# SCH_arduino-nano-every-sheild_2024-02-21.net
KiCad netlist of a schematic drawn in EasyEDA
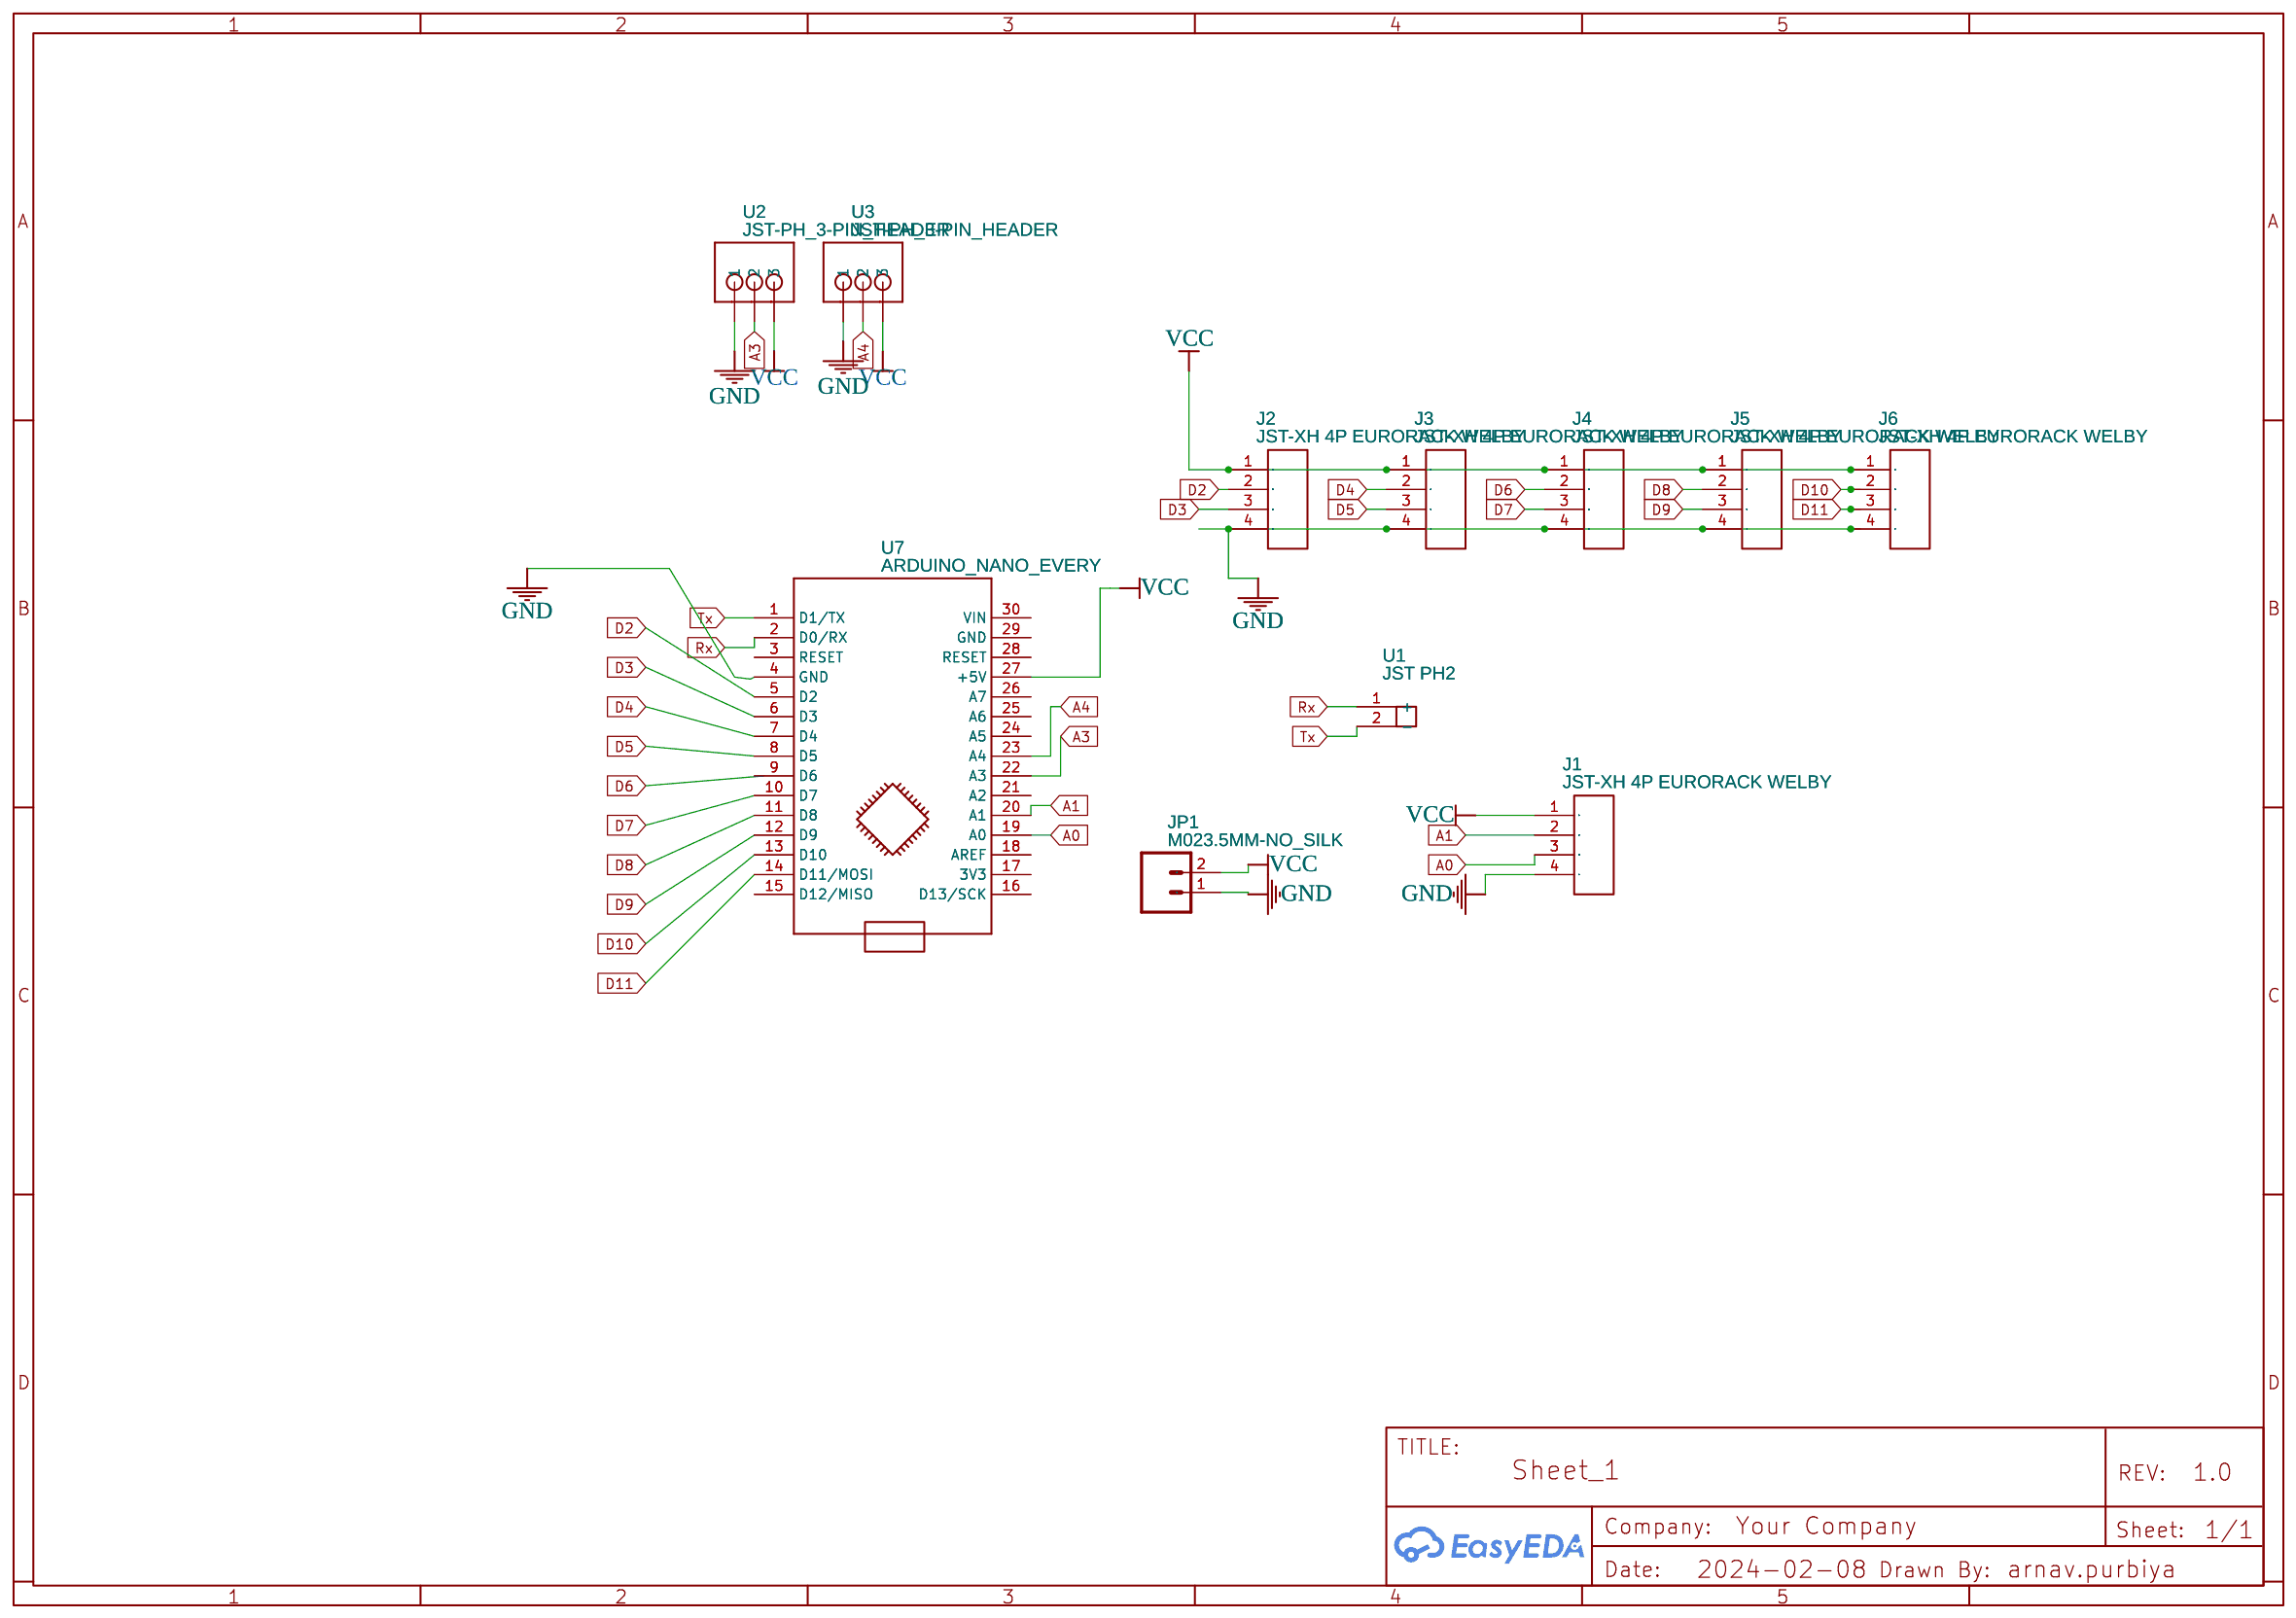
[diagram p0: schematic sheet]

(export (version "E")
  (design (tool "Eeschema 10.0.6"))
  (components
    (comp (ref "J1")
      (value "JST-XH 4P EURORACK WELBY")
      (libsource (lib "") (part "JST-XH 4P EURORACK WELBY"))
    )
    (comp (ref "J2")
      (value "JST-XH 4P EURORACK WELBY")
      (libsource (lib "") (part "JST-XH 4P EURORACK WELBY"))
    )
    (comp (ref "J3")
      (value "JST-XH 4P EURORACK WELBY")
      (libsource (lib "") (part "JST-XH 4P EURORACK WELBY"))
    )
    (comp (ref "J4")
      (value "JST-XH 4P EURORACK WELBY")
      (libsource (lib "") (part "JST-XH 4P EURORACK WELBY"))
    )
    (comp (ref "J5")
      (value "JST-XH 4P EURORACK WELBY")
      (libsource (lib "") (part "JST-XH 4P EURORACK WELBY"))
    )
    (comp (ref "J6")
      (value "JST-XH 4P EURORACK WELBY")
      (libsource (lib "") (part "JST-XH 4P EURORACK WELBY"))
    )
    (comp (ref "JP1") (value "M023.5MM-NO_SILK") (libsource (lib "") (part "M023.5MM-NO_SILK")))
    (comp (ref "U1") (value "JST PH2") (libsource (lib "") (part "JST PH2")))
    (comp (ref "U2") (value "JST-PH_3-PIN_HEADER") (libsource (lib "") (part "JST-PH_3-PIN_HEADER")))
    (comp (ref "U3") (value "JST-PH_3-PIN_HEADER") (libsource (lib "") (part "JST-PH_3-PIN_HEADER")))
    (comp (ref "U7") (value "ARDUINO_NANO_EVERY") (libsource (lib "") (part "ARDUINO_NANO_EVERY")))
  )
  (nets
    (net (code "1") (name "A0") (class "Default")
      (node (ref "J1") (pin "3") (pinfunction "3_3") (pintype "unspecified"))
      (node (ref "U7") (pin "19") (pinfunction "A0_19") (pintype "unspecified"))
    )
    (net (code "2") (name "A1") (class "Default")
      (node (ref "J1") (pin "2") (pinfunction "2_2") (pintype "unspecified"))
      (node (ref "U7") (pin "20") (pinfunction "A1_20") (pintype "unspecified"))
    )
    (net (code "3") (name "A3") (class "Default")
      (node (ref "U2") (pin "P2") (pinfunction "2_P2") (pintype "unspecified"))
      (node (ref "U7") (pin "22") (pinfunction "A3_22") (pintype "unspecified"))
    )
    (net (code "4") (name "A4") (class "Default")
      (node (ref "U3") (pin "P2") (pinfunction "2_P2") (pintype "unspecified"))
      (node (ref "U7") (pin "23") (pinfunction "A4_23") (pintype "unspecified"))
    )
    (net (code "5") (name "D2") (class "Default")
      (node (ref "J2") (pin "2") (pinfunction "2_2") (pintype "unspecified"))
      (node (ref "U7") (pin "5") (pinfunction "D2_5") (pintype "unspecified"))
    )
    (net (code "6") (name "D3") (class "Default")
      (node (ref "J2") (pin "3") (pinfunction "3_3") (pintype "unspecified"))
      (node (ref "U7") (pin "6") (pinfunction "D3_6") (pintype "unspecified"))
    )
    (net (code "7") (name "D4") (class "Default")
      (node (ref "J3") (pin "2") (pinfunction "2_2") (pintype "unspecified"))
      (node (ref "U7") (pin "7") (pinfunction "D4_7") (pintype "unspecified"))
    )
    (net (code "8") (name "D5") (class "Default")
      (node (ref "J3") (pin "3") (pinfunction "3_3") (pintype "unspecified"))
      (node (ref "U7") (pin "8") (pinfunction "D5_8") (pintype "unspecified"))
    )
    (net (code "9") (name "D6") (class "Default")
      (node (ref "J4") (pin "2") (pinfunction "2_2") (pintype "unspecified"))
    )
    (net (code "10") (name "D7") (class "Default")
      (node (ref "J4") (pin "3") (pinfunction "3_3") (pintype "unspecified"))
      (node (ref "U7") (pin "10") (pinfunction "D7_10") (pintype "unspecified"))
    )
    (net (code "11") (name "D8") (class "Default")
      (node (ref "J5") (pin "2") (pinfunction "2_2") (pintype "unspecified"))
      (node (ref "U7") (pin "11") (pinfunction "D8_11") (pintype "unspecified"))
    )
    (net (code "12") (name "D9") (class "Default")
      (node (ref "J5") (pin "3") (pinfunction "3_3") (pintype "unspecified"))
      (node (ref "U7") (pin "12") (pinfunction "D9_12") (pintype "unspecified"))
    )
    (net (code "13") (name "D10") (class "Default")
      (node (ref "J6") (pin "2") (pinfunction "2_2") (pintype "unspecified"))
      (node (ref "U7") (pin "13") (pinfunction "D10_13") (pintype "unspecified"))
    )
    (net (code "14") (name "D11") (class "Default")
      (node (ref "J6") (pin "3") (pinfunction "3_3") (pintype "unspecified"))
      (node (ref "U7") (pin "14") (pinfunction "D11/MOSI_14") (pintype "unspecified"))
    )
    (net (code "15") (name "GND") (class "Default")
      (node (ref "J1") (pin "4") (pinfunction "4_4") (pintype "unspecified"))
      (node (ref "J2") (pin "4") (pinfunction "4_4") (pintype "unspecified"))
      (node (ref "J3") (pin "4") (pinfunction "4_4") (pintype "unspecified"))
      (node (ref "J4") (pin "4") (pinfunction "4_4") (pintype "unspecified"))
      (node (ref "J5") (pin "4") (pinfunction "4_4") (pintype "unspecified"))
      (node (ref "J6") (pin "4") (pinfunction "4_4") (pintype "unspecified"))
      (node (ref "JP1") (pin "1") (pinfunction "1_1") (pintype "bidirectional"))
      (node (ref "U2") (pin "P1") (pinfunction "1_P1") (pintype "unspecified"))
      (node (ref "U3") (pin "P1") (pinfunction "1_P1") (pintype "unspecified"))
      (node (ref "U7") (pin "4") (pinfunction "GND_4") (pintype "unspecified"))
    )
    (net (code "16") (name "Rx") (class "Default")
      (node (ref "U1") (pin "1") (pinfunction "+_1") (pintype "unspecified"))
      (node (ref "U7") (pin "2") (pinfunction "D0/RX_2") (pintype "unspecified"))
    )
    (net (code "17") (name "Tx") (class "Default")
      (node (ref "U1") (pin "2") (pinfunction "-_2") (pintype "unspecified"))
      (node (ref "U7") (pin "1") (pinfunction "D1/TX_1") (pintype "unspecified"))
    )
    (net (code "18") (name "VCC") (class "Default")
      (node (ref "J1") (pin "1") (pinfunction "1_1") (pintype "unspecified"))
      (node (ref "J2") (pin "1") (pinfunction "1_1") (pintype "unspecified"))
      (node (ref "J3") (pin "1") (pinfunction "1_1") (pintype "unspecified"))
      (node (ref "J4") (pin "1") (pinfunction "1_1") (pintype "unspecified"))
      (node (ref "J5") (pin "1") (pinfunction "1_1") (pintype "unspecified"))
      (node (ref "J6") (pin "1") (pinfunction "1_1") (pintype "unspecified"))
      (node (ref "JP1") (pin "2") (pinfunction "2_2") (pintype "bidirectional"))
      (node (ref "U2") (pin "P3") (pinfunction "3_P3") (pintype "unspecified"))
      (node (ref "U3") (pin "P3") (pinfunction "3_P3") (pintype "unspecified"))
      (node (ref "U7") (pin "27") (pinfunction "+5V_27") (pintype "unspecified"))
    )
    (net (code "19") (name "unconnected-(U7-3V3-Pad17)") (class "Default")
      (node (ref "U7") (pin "17") (pinfunction "3V3_17") (pintype "unspecified"))
    )
    (net (code "20") (name "unconnected-(U7-A2-Pad21)") (class "Default")
      (node (ref "U7") (pin "21") (pinfunction "A2_21") (pintype "unspecified"))
    )
    (net (code "21") (name "unconnected-(U7-A5-Pad24)") (class "Default")
      (node (ref "U7") (pin "24") (pinfunction "A5_24") (pintype "unspecified"))
    )
    (net (code "22") (name "unconnected-(U7-A6-Pad25)") (class "Default")
      (node (ref "U7") (pin "25") (pinfunction "A6_25") (pintype "unspecified"))
    )
    (net (code "23") (name "unconnected-(U7-A7-Pad26)") (class "Default")
      (node (ref "U7") (pin "26") (pinfunction "A7_26") (pintype "unspecified"))
    )
    (net (code "24") (name "unconnected-(U7-AREF-Pad18)") (class "Default")
      (node (ref "U7") (pin "18") (pinfunction "AREF_18") (pintype "unspecified"))
    )
    (net (code "25") (name "unconnected-(U7-D6-Pad9)") (class "Default")
      (node (ref "U7") (pin "9") (pinfunction "D6_9") (pintype "unspecified"))
    )
    (net (code "26") (name "unconnected-(U7-D12{slash}MISO-Pad15)") (class "Default")
      (node (ref "U7") (pin "15") (pinfunction "D12/MISO_15") (pintype "unspecified"))
    )
    (net (code "27") (name "unconnected-(U7-D13{slash}SCK-Pad16)") (class "Default")
      (node (ref "U7") (pin "16") (pinfunction "D13/SCK_16") (pintype "unspecified"))
    )
    (net (code "28") (name "unconnected-(U7-GND-Pad29)") (class "Default")
      (node (ref "U7") (pin "29") (pinfunction "GND_29") (pintype "unspecified"))
    )
    (net (code "29") (name "unconnected-(U7-RESET-Pad3)") (class "Default")
      (node (ref "U7") (pin "3") (pinfunction "RESET_3") (pintype "unspecified"))
    )
    (net (code "30") (name "unconnected-(U7-RESET-Pad28)") (class "Default")
      (node (ref "U7") (pin "28") (pinfunction "RESET_28") (pintype "unspecified"))
    )
    (net (code "31") (name "unconnected-(U7-VIN-Pad30)") (class "Default")
      (node (ref "U7") (pin "30") (pinfunction "VIN_30") (pintype "unspecified"))
    )
  )
)
